# linvinus_ups.net
KiCad netlist of a schematic drawn in EAGLE
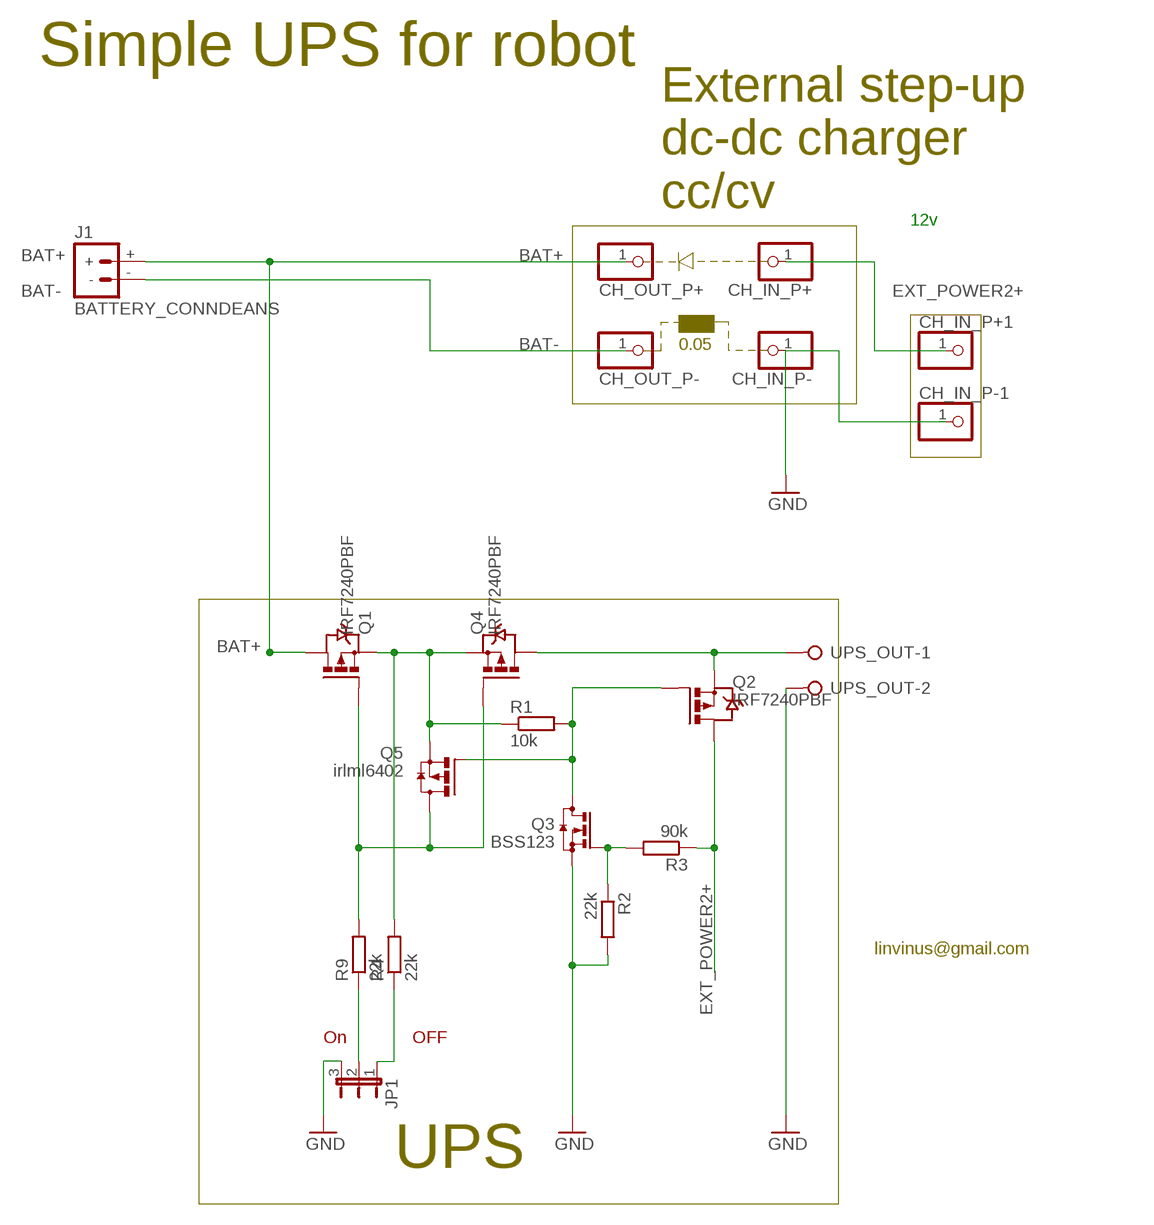
[diagram p0: schematic, sheet 1]

(export (version "E")
  (design (tool "Eeschema 10.0.6"))
  (components
    (comp (ref "CH_IN_P+")
      (value "PINHD-1X1")
      (footprint "eagle-import:1X01")
      (libsource (lib "eagle-import") (part "PINHD-1X1"))
    )
    (comp (ref "CH_IN_P+1")
      (value "PINHD-1X1")
      (footprint "eagle-import:1X01")
      (libsource (lib "eagle-import") (part "PINHD-1X1"))
    )
    (comp (ref "CH_IN_P-")
      (value "PINHD-1X1")
      (footprint "eagle-import:1X01")
      (libsource (lib "eagle-import") (part "PINHD-1X1"))
    )
    (comp (ref "CH_IN_P-1")
      (value "PINHD-1X1")
      (footprint "eagle-import:1X01")
      (libsource (lib "eagle-import") (part "PINHD-1X1"))
    )
    (comp (ref "CH_OUT_P+")
      (value "PINHD-1X1")
      (footprint "eagle-import:1X01")
      (libsource (lib "eagle-import") (part "PINHD-1X1"))
    )
    (comp (ref "CH_OUT_P-")
      (value "PINHD-1X1")
      (footprint "eagle-import:1X01")
      (libsource (lib "eagle-import") (part "PINHD-1X1"))
    )
    (comp (ref "J1")
      (value "BATTERY_CONNDEANS")
      (footprint "eagle-import:DEANS")
      (libsource (lib "eagle-import") (part "BATTERY_CONNDEANS"))
    )
    (comp (ref "JP1")
      (value "JP2E")
      (footprint "eagle-import:JP2")
      (libsource (lib "eagle-import") (part "JP2E"))
    )
    (comp (ref "Q1")
      (value "IRF7240PBF")
      (footprint "eagle-import:SO-08")
      (libsource (lib "eagle-import") (part "P-MOSFET-SO8"))
    )
    (comp (ref "Q2")
      (value "IRF7240PBF")
      (footprint "eagle-import:SO-08")
      (libsource (lib "eagle-import") (part "P-MOSFET-SO8"))
    )
    (comp (ref "Q3")
      (value "BSS123")
      (footprint "eagle-import:SOT23")
      (libsource (lib "eagle-import") (part "BSS123"))
    )
    (comp (ref "Q4")
      (value "IRF7240PBF")
      (footprint "eagle-import:SO-08")
      (libsource (lib "eagle-import") (part "P-MOSFET-SO8"))
    )
    (comp (ref "Q5")
      (value "irlml6402")
      (footprint "eagle-import:SUPER-SOT3")
      (libsource (lib "eagle-import") (part "FDN360P"))
    )
    (comp (ref "R1")
      (value "10k")
      (footprint "eagle-import:R0805")
      (libsource (lib "eagle-import") (part "R-EU_R0805"))
    )
    (comp (ref "R2")
      (value "22k")
      (footprint "eagle-import:R0805")
      (libsource (lib "eagle-import") (part "R-EU_R0805"))
    )
    (comp (ref "R3")
      (value "90k")
      (footprint "eagle-import:R0805")
      (libsource (lib "eagle-import") (part "R-EU_R0805"))
    )
    (comp (ref "R4")
      (value "22k")
      (footprint "eagle-import:R0805")
      (libsource (lib "eagle-import") (part "R-EU_R0805"))
    )
    (comp (ref "R9")
      (value "22k")
      (footprint "eagle-import:R0805")
      (libsource (lib "eagle-import") (part "R-EU_R0805"))
    )
    (comp (ref "UPS_OUT")
      (value "W237-02P")
      (footprint "eagle-import:W237-132")
      (libsource (lib "eagle-import") (part "W237-02P"))
    )
  )
  (nets
    (net (code "1") (name "/BAT+") (class "Default")
      (node (ref "CH_OUT_P+") (pin "1") (pinfunction "1_1") (pintype "passive"))
      (node (ref "J1") (pin "+") (pinfunction "+_+") (pintype "passive"))
      (node (ref "Q1") (pin "5") (pinfunction "D_5") (pintype "passive"))
      (node (ref "Q1") (pin "6") (pinfunction "D_6") (pintype "passive"))
      (node (ref "Q1") (pin "7") (pinfunction "D_7") (pintype "passive"))
      (node (ref "Q1") (pin "8") (pinfunction "D_8") (pintype "passive"))
    )
    (net (code "2") (name "/BAT-") (class "Default")
      (node (ref "CH_OUT_P-") (pin "1") (pinfunction "1_1") (pintype "passive"))
      (node (ref "J1") (pin "-") (pinfunction "-_-") (pintype "passive"))
    )
    (net (code "3") (name "/EXT_POWER2+") (class "Default")
      (node (ref "CH_IN_P+") (pin "1") (pinfunction "1_1") (pintype "passive"))
      (node (ref "CH_IN_P+1") (pin "1") (pinfunction "1_1") (pintype "passive"))
      (node (ref "Q2") (pin "5") (pinfunction "D_5") (pintype "passive"))
      (node (ref "Q2") (pin "6") (pinfunction "D_6") (pintype "passive"))
      (node (ref "Q2") (pin "7") (pinfunction "D_7") (pintype "passive"))
      (node (ref "Q2") (pin "8") (pinfunction "D_8") (pintype "passive"))
      (node (ref "R3") (pin "1") (pinfunction "1_1") (pintype "passive"))
    )
    (net (code "4") (name "GND") (class "Default")
      (node (ref "CH_IN_P-") (pin "1") (pinfunction "1_1") (pintype "passive"))
      (node (ref "CH_IN_P-1") (pin "1") (pinfunction "1_1") (pintype "passive"))
      (node (ref "JP1") (pin "3") (pinfunction "3_3") (pintype "passive"))
      (node (ref "Q3") (pin "2") (pinfunction "S_2") (pintype "passive"))
      (node (ref "R2") (pin "2") (pinfunction "2_2") (pintype "passive"))
      (node (ref "UPS_OUT") (pin "2") (pinfunction "KL_2") (pintype "passive"))
    )
    (net (code "5") (name "Net-(JP1-Pad1)") (class "Default")
      (node (ref "JP1") (pin "1") (pinfunction "1_1") (pintype "passive"))
      (node (ref "R4") (pin "1") (pinfunction "1_1") (pintype "passive"))
    )
    (net (code "6") (name "Net-(JP1-Pad2)") (class "Default")
      (node (ref "JP1") (pin "2") (pinfunction "2_2") (pintype "passive"))
      (node (ref "R9") (pin "1") (pinfunction "1_1") (pintype "passive"))
    )
    (net (code "7") (name "Net-(Q1-G)") (class "Default")
      (node (ref "Q1") (pin "4") (pinfunction "G_4") (pintype "passive"))
      (node (ref "Q4") (pin "4") (pinfunction "G_4") (pintype "passive"))
      (node (ref "Q5") (pin "3") (pinfunction "D_3") (pintype "passive"))
      (node (ref "R9") (pin "2") (pinfunction "2_2") (pintype "passive"))
    )
    (net (code "8") (name "Net-(Q2-G)") (class "Default")
      (node (ref "Q2") (pin "4") (pinfunction "G_4") (pintype "passive"))
      (node (ref "Q3") (pin "3") (pinfunction "D_3") (pintype "passive"))
      (node (ref "Q5") (pin "1") (pinfunction "G_1") (pintype "passive"))
      (node (ref "R1") (pin "2") (pinfunction "2_2") (pintype "passive"))
    )
    (net (code "9") (name "Net-(Q3-G)") (class "Default")
      (node (ref "Q3") (pin "1") (pinfunction "G_1") (pintype "passive"))
      (node (ref "R2") (pin "1") (pinfunction "1_1") (pintype "passive"))
      (node (ref "R3") (pin "2") (pinfunction "2_2") (pintype "passive"))
    )
    (net (code "10") (name "Net-(Q5-S)") (class "Default")
      (node (ref "Q1") (pin "1") (pinfunction "S_1") (pintype "passive"))
      (node (ref "Q1") (pin "2") (pinfunction "S_2") (pintype "passive"))
      (node (ref "Q1") (pin "3") (pinfunction "S_3") (pintype "passive"))
      (node (ref "Q4") (pin "1") (pinfunction "S_1") (pintype "passive"))
      (node (ref "Q4") (pin "2") (pinfunction "S_2") (pintype "passive"))
      (node (ref "Q4") (pin "3") (pinfunction "S_3") (pintype "passive"))
      (node (ref "Q5") (pin "2") (pinfunction "S_2") (pintype "passive"))
      (node (ref "R1") (pin "1") (pinfunction "1_1") (pintype "passive"))
      (node (ref "R4") (pin "2") (pinfunction "2_2") (pintype "passive"))
    )
    (net (code "11") (name "Net-(UPS_OUTA-KL)") (class "Default")
      (node (ref "Q2") (pin "1") (pinfunction "S_1") (pintype "passive"))
      (node (ref "Q2") (pin "2") (pinfunction "S_2") (pintype "passive"))
      (node (ref "Q2") (pin "3") (pinfunction "S_3") (pintype "passive"))
      (node (ref "Q4") (pin "5") (pinfunction "D_5") (pintype "passive"))
      (node (ref "Q4") (pin "6") (pinfunction "D_6") (pintype "passive"))
      (node (ref "Q4") (pin "7") (pinfunction "D_7") (pintype "passive"))
      (node (ref "Q4") (pin "8") (pinfunction "D_8") (pintype "passive"))
      (node (ref "UPS_OUT") (pin "1") (pinfunction "KL_1") (pintype "passive"))
    )
  )
)
